# PCIe.net
KiCad netlist of a schematic drawn in Altium Designer
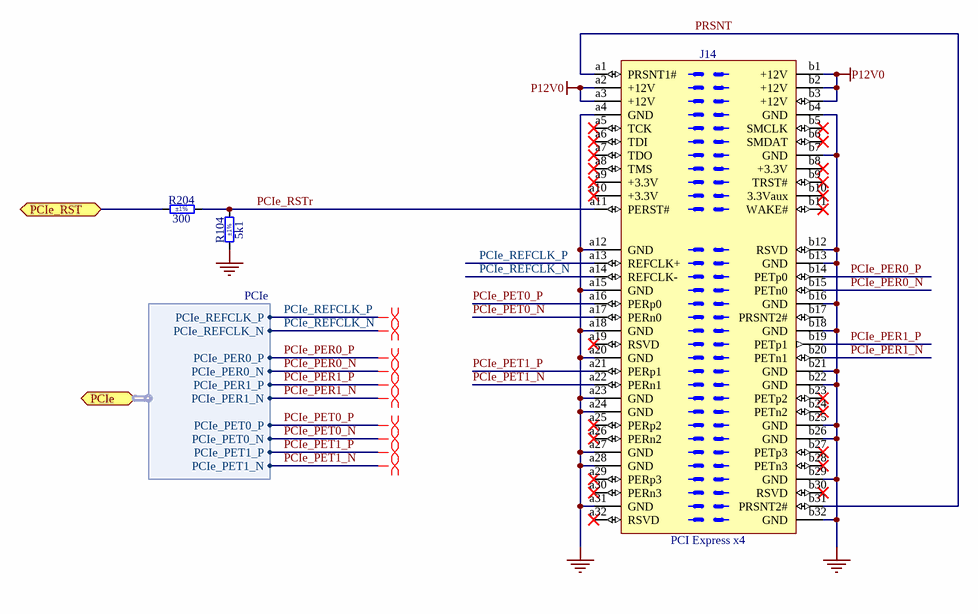
[diagram p0: PCIe.SchDoc]

(export (version "E")
  (design (tool "Eeschema 10.0.6"))
  (components
    (comp (ref "J14")
      (value "PCI Express x4")
      (footprint "PCI Express x4")
      (description "64 contacts Board Eddge PCI Express x4 Connector")
      (fields (field (name "MANUFACTURER") "PCI-SIG") (field (name "AUTHOR") "CERN DEM JLC"))
      (libsource (lib "Connectors") (part "PCI Express x4 Male"))
    )
    (comp (ref "R104")
      (value "5k1")
      (footprint "RESC1005X40N")
      (description "Resistor - 1%")
      (fields
        (field (name "TOLERANCE") "±1%")
        (field (name "PART NUMBER") "R0402_5K1_1%_0.0625W_100PPM")
        (field (name "POWER") "0.0625W")
        (field (name "AUTHOR") "CERN DEM JLC")
      )
      (libsource (lib "Resistors") (part "Resistor - 1%"))
    )
    (comp (ref "R204")
      (value "300")
      (footprint "RESC1005X40N")
      (description "Resistor - 1%")
      (fields
        (field (name "TOLERANCE") "±1%")
        (field (name "PART NUMBER") "R0402_300R_1%_0.0625W_100PPM")
        (field (name "POWER") "0.0625W")
        (field (name "AUTHOR") "CERN DEM JLC")
      )
      (libsource (lib "Resistors") (part "Resistor - 1%"))
    )
  )
  (nets
    (net (code "2") (name "/PCIe_PER0_N") (class "Default")
      (node (ref "J14") (pin "b15") (pinfunction "PETn0_b15") (pintype "bidirectional"))
    )
    (net (code "3") (name "/PCIe_PER0_P") (class "Default")
      (node (ref "J14") (pin "b14") (pinfunction "PETp0_b14") (pintype "bidirectional"))
    )
    (net (code "4") (name "/PCIe_PER1_N") (class "Default")
      (node (ref "J14") (pin "b20") (pinfunction "PETn1_b20") (pintype "bidirectional"))
    )
    (net (code "5") (name "/PCIe_PER1_P") (class "Default")
      (node (ref "J14") (pin "b19") (pinfunction "PETp1_b19") (pintype "output"))
    )
    (net (code "6") (name "/PCIe_PET0_N") (class "Default")
      (node (ref "J14") (pin "a17") (pinfunction "PERn0_a17") (pintype "bidirectional"))
    )
    (net (code "7") (name "/PCIe_PET0_P") (class "Default")
      (node (ref "J14") (pin "a16") (pinfunction "PERp0_a16") (pintype "bidirectional"))
    )
    (net (code "8") (name "/PCIe_PET1_N") (class "Default")
      (node (ref "J14") (pin "a22") (pinfunction "PERn1_a22") (pintype "bidirectional"))
    )
    (net (code "9") (name "/PCIe_PET1_P") (class "Default")
      (node (ref "J14") (pin "a21") (pinfunction "PERp1_a21") (pintype "bidirectional"))
    )
    (net (code "10") (name "/PCIe_REFCLK_N") (class "Default")
      (node (ref "J14") (pin "a14") (pinfunction "REFCLK-_a14") (pintype "bidirectional"))
    )
    (net (code "11") (name "/PCIe_REFCLK_P") (class "Default")
      (node (ref "J14") (pin "a13") (pinfunction "REFCLK+_a13") (pintype "bidirectional"))
    )
    (net (code "12") (name "/PCIe_RST") (class "Default")
      (node (ref "R204") (pin "1") (pinfunction "1_1") (pintype "passive"))
    )
    (net (code "13") (name "/PCIe_RSTr") (class "Default")
      (node (ref "J14") (pin "a11") (pinfunction "PERST#_a11") (pintype "bidirectional"))
      (node (ref "R104") (pin "2") (pinfunction "2_2") (pintype "passive"))
      (node (ref "R204") (pin "2") (pinfunction "2_2") (pintype "passive"))
    )
    (net (code "14") (name "/PRSNT") (class "Default")
      (node (ref "J14") (pin "a1") (pinfunction "PRSNT1#_a1") (pintype "bidirectional"))
      (node (ref "J14") (pin "b31") (pinfunction "PRSNT2#_b31") (pintype "bidirectional"))
    )
    (net (code "16") (name "GND") (class "Default")
      (node (ref "J14") (pin "a12") (pinfunction "GND_a12") (pintype "power_in"))
      (node (ref "J14") (pin "a15") (pinfunction "GND_a15") (pintype "power_in"))
      (node (ref "J14") (pin "a18") (pinfunction "GND_a18") (pintype "power_in"))
      (node (ref "J14") (pin "a20") (pinfunction "GND_a20") (pintype "power_in"))
      (node (ref "J14") (pin "a23") (pinfunction "GND_a23") (pintype "power_in"))
      (node (ref "J14") (pin "a24") (pinfunction "GND_a24") (pintype "power_in"))
      (node (ref "J14") (pin "a27") (pinfunction "GND_a27") (pintype "power_in"))
      (node (ref "J14") (pin "a28") (pinfunction "GND_a28") (pintype "power_in"))
      (node (ref "J14") (pin "a31") (pinfunction "GND_a31") (pintype "power_in"))
      (node (ref "J14") (pin "a4") (pinfunction "GND_a4") (pintype "power_in"))
      (node (ref "J14") (pin "b12") (pinfunction "RSVD_b12") (pintype "bidirectional"))
      (node (ref "J14") (pin "b13") (pinfunction "GND_b13") (pintype "power_in"))
      (node (ref "J14") (pin "b16") (pinfunction "GND_b16") (pintype "power_in"))
      (node (ref "J14") (pin "b18") (pinfunction "GND_b18") (pintype "power_in"))
      (node (ref "J14") (pin "b21") (pinfunction "GND_b21") (pintype "power_in"))
      (node (ref "J14") (pin "b22") (pinfunction "GND_b22") (pintype "power_in"))
      (node (ref "J14") (pin "b25") (pinfunction "GND_b25") (pintype "power_in"))
      (node (ref "J14") (pin "b26") (pinfunction "GND_b26") (pintype "power_in"))
      (node (ref "J14") (pin "b29") (pinfunction "GND_b29") (pintype "power_in"))
      (node (ref "J14") (pin "b32") (pinfunction "GND_b32") (pintype "power_in"))
      (node (ref "J14") (pin "b4") (pinfunction "GND_b4") (pintype "power_in"))
      (node (ref "J14") (pin "b7") (pinfunction "GND_b7") (pintype "power_in"))
      (node (ref "R104") (pin "1") (pinfunction "1_1") (pintype "passive"))
    )
    (net (code "17") (name "P12V0") (class "Default")
      (node (ref "J14") (pin "a2") (pinfunction "+12V_a2") (pintype "power_in"))
      (node (ref "J14") (pin "a3") (pinfunction "+12V_a3") (pintype "power_in"))
      (node (ref "J14") (pin "b1") (pinfunction "+12V_b1") (pintype "power_in"))
      (node (ref "J14") (pin "b2") (pinfunction "+12V_b2") (pintype "power_in"))
      (node (ref "J14") (pin "b3") (pinfunction "+12V_b3") (pintype "bidirectional"))
    )
    (net (code "18") (name "unconnected-(J14-+3.3V-Pada9)") (class "Default")
      (node (ref "J14") (pin "a9") (pinfunction "+3.3V_a9") (pintype "power_in+no_connect"))
    )
    (net (code "19") (name "unconnected-(J14-+3.3V-Pada10)") (class "Default")
      (node (ref "J14") (pin "a10") (pinfunction "+3.3V_a10") (pintype "power_in+no_connect"))
    )
    (net (code "20") (name "unconnected-(J14-+3.3V-Padb8)") (class "Default")
      (node (ref "J14") (pin "b8") (pinfunction "+3.3V_b8") (pintype "power_in+no_connect"))
    )
    (net (code "21") (name "unconnected-(J14-3.3Vaux-Padb10)") (class "Default")
      (node (ref "J14") (pin "b10") (pinfunction "3.3Vaux_b10") (pintype "power_in+no_connect"))
    )
    (net (code "22") (name "unconnected-(J14-PERn2-Pada26)") (class "Default")
      (node (ref "J14") (pin "a26") (pinfunction "PERn2_a26") (pintype "bidirectional+no_connect"))
    )
    (net (code "23") (name "unconnected-(J14-PERn3-Pada30)") (class "Default")
      (node (ref "J14") (pin "a30") (pinfunction "PERn3_a30") (pintype "bidirectional+no_connect"))
    )
    (net (code "24") (name "unconnected-(J14-PERp2-Pada25)") (class "Default")
      (node (ref "J14") (pin "a25") (pinfunction "PERp2_a25") (pintype "bidirectional+no_connect"))
    )
    (net (code "25") (name "unconnected-(J14-PERp3-Pada29)") (class "Default")
      (node (ref "J14") (pin "a29") (pinfunction "PERp3_a29") (pintype "bidirectional+no_connect"))
    )
    (net (code "26") (name "unconnected-(J14-PETn2-Padb24)") (class "Default")
      (node (ref "J14") (pin "b24") (pinfunction "PETn2_b24") (pintype "bidirectional+no_connect"))
    )
    (net (code "27") (name "unconnected-(J14-PETn3-Padb28)") (class "Default")
      (node (ref "J14") (pin "b28") (pinfunction "PETn3_b28") (pintype "bidirectional+no_connect"))
    )
    (net (code "28") (name "unconnected-(J14-PETp2-Padb23)") (class "Default")
      (node (ref "J14") (pin "b23") (pinfunction "PETp2_b23") (pintype "bidirectional+no_connect"))
    )
    (net (code "29") (name "unconnected-(J14-PETp3-Padb27)") (class "Default")
      (node (ref "J14") (pin "b27") (pinfunction "PETp3_b27") (pintype "bidirectional+no_connect"))
    )
    (net (code "30") (name "unconnected-(J14-PRSNT2#-Padb17)") (class "Default")
      (node (ref "J14") (pin "b17") (pinfunction "PRSNT2#_b17") (pintype "bidirectional"))
    )
    (net (code "31") (name "unconnected-(J14-RSVD-Pada19)") (class "Default")
      (node (ref "J14") (pin "a19") (pinfunction "RSVD_a19") (pintype "bidirectional+no_connect"))
    )
    (net (code "32") (name "unconnected-(J14-RSVD-Pada32)") (class "Default")
      (node (ref "J14") (pin "a32") (pinfunction "RSVD_a32") (pintype "bidirectional+no_connect"))
    )
    (net (code "33") (name "unconnected-(J14-RSVD-Padb30)") (class "Default")
      (node (ref "J14") (pin "b30") (pinfunction "RSVD_b30") (pintype "bidirectional+no_connect"))
    )
    (net (code "34") (name "unconnected-(J14-SMCLK-Padb5)") (class "Default")
      (node (ref "J14") (pin "b5") (pinfunction "SMCLK_b5") (pintype "bidirectional+no_connect"))
    )
    (net (code "35") (name "unconnected-(J14-SMDAT-Padb6)") (class "Default")
      (node (ref "J14") (pin "b6") (pinfunction "SMDAT_b6") (pintype "bidirectional+no_connect"))
    )
    (net (code "36") (name "unconnected-(J14-TCK-Pada5)") (class "Default")
      (node (ref "J14") (pin "a5") (pinfunction "TCK_a5") (pintype "bidirectional+no_connect"))
    )
    (net (code "37") (name "unconnected-(J14-TDI-Pada6)") (class "Default")
      (node (ref "J14") (pin "a6") (pinfunction "TDI_a6") (pintype "bidirectional+no_connect"))
    )
    (net (code "38") (name "unconnected-(J14-TDO-Pada7)") (class "Default")
      (node (ref "J14") (pin "a7") (pinfunction "TDO_a7") (pintype "bidirectional+no_connect"))
    )
    (net (code "39") (name "unconnected-(J14-TMS-Pada8)") (class "Default")
      (node (ref "J14") (pin "a8") (pinfunction "TMS_a8") (pintype "bidirectional+no_connect"))
    )
    (net (code "40") (name "unconnected-(J14-TRST#-Padb9)") (class "Default")
      (node (ref "J14") (pin "b9") (pinfunction "TRST#_b9") (pintype "bidirectional+no_connect"))
    )
    (net (code "41") (name "unconnected-(J14-WAKE#-Padb11)") (class "Default")
      (node (ref "J14") (pin "b11") (pinfunction "WAKE#_b11") (pintype "bidirectional+no_connect"))
    )
  )
)
